# whoop65mm.net
KiCad netlist of a schematic drawn in EAGLE
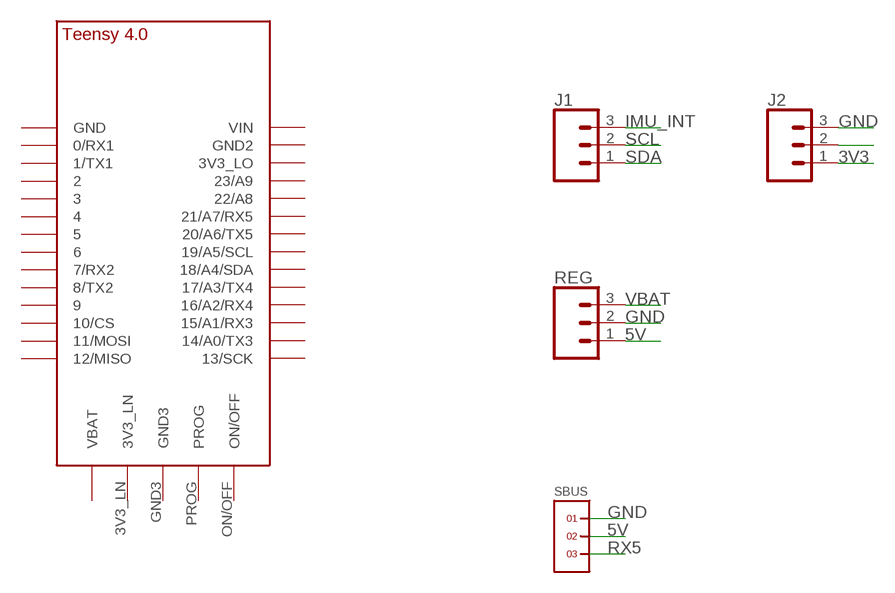
[diagram p0: schematic, sheet 1]

(export (version "E")
  (design (tool "Eeschema 10.0.6"))
  (components
    (comp (ref "J1")
      (value "CONN_031X03_NO_SILK")
      (footprint "eagle-import:1X03_NO_SILK")
      (libsource (lib "eagle-import") (part "CONN_031X03_NO_SILK"))
    )
    (comp (ref "J2")
      (value "CONN_031X03_NO_SILK")
      (footprint "eagle-import:1X03_NO_SILK")
      (libsource (lib "eagle-import") (part "CONN_031X03_NO_SILK"))
    )
    (comp (ref "REG")
      (value "CONN_031X03_NO_SILK")
      (footprint "eagle-import:1X03_NO_SILK")
      (libsource (lib "eagle-import") (part "CONN_031X03_NO_SILK"))
    )
    (comp (ref "SBUS")
      (value "1X3")
      (footprint "eagle-import:1X3")
      (libsource (lib "eagle-import") (part "1X3"))
    )
    (comp (ref "U$1")
      (value "TEENSY_4.0")
      (footprint "eagle-import:TEENSY_4.0")
      (libsource (lib "eagle-import") (part "TEENSY_4.0"))
    )
  )
  (nets
    (net (code "1") (name "/3V3") (class "Default")
      (node (ref "J2") (pin "1") (pinfunction "1_1") (pintype "passive"))
    )
    (net (code "2") (name "/5V") (class "Default")
      (node (ref "REG") (pin "1") (pinfunction "1_1") (pintype "passive"))
      (node (ref "SBUS") (pin "2") (pinfunction "2_2") (pintype "bidirectional"))
    )
    (net (code "3") (name "/GND") (class "Default")
      (node (ref "J2") (pin "3") (pinfunction "3_3") (pintype "passive"))
      (node (ref "REG") (pin "2") (pinfunction "2_2") (pintype "passive"))
      (node (ref "SBUS") (pin "1") (pinfunction "1_1") (pintype "bidirectional"))
    )
    (net (code "4") (name "/IMU_INT") (class "Default")
      (node (ref "J1") (pin "3") (pinfunction "3_3") (pintype "passive"))
    )
    (net (code "5") (name "/RX5") (class "Default")
      (node (ref "SBUS") (pin "3") (pinfunction "3_3") (pintype "bidirectional"))
    )
    (net (code "6") (name "/SCL") (class "Default")
      (node (ref "J1") (pin "2") (pinfunction "2_2") (pintype "passive"))
    )
    (net (code "7") (name "/SDA") (class "Default")
      (node (ref "J1") (pin "1") (pinfunction "1_1") (pintype "passive"))
    )
    (net (code "8") (name "/VBAT") (class "Default")
      (node (ref "REG") (pin "3") (pinfunction "3_3") (pintype "passive"))
    )
    (net (code "9") (name "unconnected-(J2-Pad2)") (class "Default")
      (node (ref "J2") (pin "2") (pinfunction "2_2") (pintype "passive"))
    )
    (net (code "10") (name "unconnected-(U$1-0{slash}RX1-Pad0{slash}RX)") (class "Default")
      (node (ref "U$1") (pin "0/RX") (pinfunction "0/RX1_0/RX") (pintype "bidirectional"))
    )
    (net (code "11") (name "unconnected-(U$1-1{slash}TX1-Pad1{slash}TX)") (class "Default")
      (node (ref "U$1") (pin "1/TX") (pinfunction "1/TX1_1/TX") (pintype "bidirectional"))
    )
    (net (code "12") (name "unconnected-(U$1-3-Pad3{slash}CANTX)") (class "Default")
      (node (ref "U$1") (pin "3/CANTX") (pinfunction "3_3/CANTX") (pintype "bidirectional"))
    )
    (net (code "13") (name "unconnected-(U$1-4-Pad4{slash}CANRX)") (class "Default")
      (node (ref "U$1") (pin "4/CANRX") (pinfunction "4_4/CANRX") (pintype "bidirectional"))
    )
    (net (code "14") (name "unconnected-(U$1-7{slash}RX2-Pad7)") (class "Default")
      (node (ref "U$1") (pin "7") (pinfunction "7/RX2_7") (pintype "bidirectional"))
    )
    (net (code "15") (name "unconnected-(U$1-8{slash}TX2-Pad8)") (class "Default")
      (node (ref "U$1") (pin "8") (pinfunction "8/TX2_8") (pintype "bidirectional"))
    )
    (net (code "16") (name "unconnected-(U$1-9-Pad9{slash}CS)") (class "Default")
      (node (ref "U$1") (pin "9/CS") (pinfunction "9_9/CS") (pintype "bidirectional"))
    )
    (net (code "17") (name "unconnected-(U$1-14{slash}A0{slash}TX3-Pad14{slash}A0)") (class "Default")
      (node (ref "U$1") (pin "14/A0") (pinfunction "14/A0/TX3_14/A0") (pintype "bidirectional"))
    )
    (net (code "18") (name "unconnected-(U$1-15{slash}A1{slash}RX3-Pad15{slash}A1)") (class "Default")
      (node (ref "U$1") (pin "15/A1") (pinfunction "15/A1/RX3_15/A1") (pintype "bidirectional"))
    )
    (net (code "19") (name "unconnected-(U$1-16{slash}A2{slash}RX4-Pad16{slash}A2)") (class "Default")
      (node (ref "U$1") (pin "16/A2") (pinfunction "16/A2/RX4_16/A2") (pintype "bidirectional"))
    )
    (net (code "20") (name "unconnected-(U$1-17{slash}A3{slash}TX4-Pad17{slash}A3)") (class "Default")
      (node (ref "U$1") (pin "17/A3") (pinfunction "17/A3/TX4_17/A3") (pintype "bidirectional"))
    )
    (net (code "21") (name "unconnected-(U$1-20{slash}A6{slash}TX5-Pad20{slash}A6)") (class "Default")
      (node (ref "U$1") (pin "20/A6") (pinfunction "20/A6/TX5_20/A6") (pintype "bidirectional"))
    )
    (net (code "22") (name "unconnected-(U$1-21{slash}A7{slash}RX5-Pad21{slash}A7)") (class "Default")
      (node (ref "U$1") (pin "21/A7") (pinfunction "21/A7/RX5_21/A7") (pintype "bidirectional"))
    )
    (net (code "23") (name "unconnected-(U$1-Pad2)") (class "Default")
      (node (ref "U$1") (pin "2") (pinfunction "2_2") (pintype "bidirectional"))
    )
    (net (code "24") (name "unconnected-(U$1-Pad3V3_LN)") (class "Default")
      (node (ref "U$1") (pin "3V3_LN") (pinfunction "3V3_LN_3V3_LN") (pintype "bidirectional"))
    )
    (net (code "25") (name "unconnected-(U$1-Pad3V3_LO)") (class "Default")
      (node (ref "U$1") (pin "3V3_LO") (pinfunction "3V3_LO_3V3_LO") (pintype "bidirectional"))
    )
    (net (code "26") (name "unconnected-(U$1-Pad5)") (class "Default")
      (node (ref "U$1") (pin "5") (pinfunction "5_5") (pintype "bidirectional"))
    )
    (net (code "27") (name "unconnected-(U$1-Pad6)") (class "Default")
      (node (ref "U$1") (pin "6") (pinfunction "6_6") (pintype "bidirectional"))
    )
    (net (code "28") (name "unconnected-(U$1-Pad10{slash}CS)") (class "Default")
      (node (ref "U$1") (pin "10/CS") (pinfunction "10/CS_10/CS") (pintype "bidirectional"))
    )
    (net (code "29") (name "unconnected-(U$1-Pad11{slash}MOSI)") (class "Default")
      (node (ref "U$1") (pin "11/MOSI") (pinfunction "11/MOSI_11/MOSI") (pintype "bidirectional"))
    )
    (net (code "30") (name "unconnected-(U$1-Pad12{slash}MISO)") (class "Default")
      (node (ref "U$1") (pin "12/MISO") (pinfunction "12/MISO_12/MISO") (pintype "bidirectional"))
    )
    (net (code "31") (name "unconnected-(U$1-Pad13{slash}SCK)") (class "Default")
      (node (ref "U$1") (pin "13/SCK") (pinfunction "13/SCK_13/SCK") (pintype "bidirectional"))
    )
    (net (code "32") (name "unconnected-(U$1-Pad18{slash}A4{slash}SDA)") (class "Default")
      (node (ref "U$1") (pin "18/A4/SDA") (pinfunction "18/A4/SDA_18/A4/SDA") (pintype "bidirectional"))
    )
    (net (code "33") (name "unconnected-(U$1-Pad19{slash}A5{slash}SCL)") (class "Default")
      (node (ref "U$1") (pin "19/A5/SCL") (pinfunction "19/A5/SCL_19/A5/SCL") (pintype "bidirectional"))
    )
    (net (code "34") (name "unconnected-(U$1-Pad22{slash}A8)") (class "Default")
      (node (ref "U$1") (pin "22/A8") (pinfunction "22/A8_22/A8") (pintype "bidirectional"))
    )
    (net (code "35") (name "unconnected-(U$1-Pad23{slash}A9)") (class "Default")
      (node (ref "U$1") (pin "23/A9") (pinfunction "23/A9_23/A9") (pintype "bidirectional"))
    )
    (net (code "36") (name "unconnected-(U$1-PadGND)") (class "Default")
      (node (ref "U$1") (pin "GND") (pinfunction "GND_GND") (pintype "bidirectional"))
    )
    (net (code "37") (name "unconnected-(U$1-PadGND2)") (class "Default")
      (node (ref "U$1") (pin "GND2") (pinfunction "GND2_GND2") (pintype "bidirectional"))
    )
    (net (code "38") (name "unconnected-(U$1-PadGND3)") (class "Default")
      (node (ref "U$1") (pin "GND3") (pinfunction "GND3_GND3") (pintype "bidirectional"))
    )
    (net (code "39") (name "unconnected-(U$1-PadON{slash}OFF)") (class "Default")
      (node (ref "U$1") (pin "ON/OFF") (pinfunction "ON/OFF_ON/OFF") (pintype "bidirectional"))
    )
    (net (code "40") (name "unconnected-(U$1-PadPROG)") (class "Default")
      (node (ref "U$1") (pin "PROG") (pinfunction "PROG_PROG") (pintype "bidirectional"))
    )
    (net (code "41") (name "unconnected-(U$1-PadVIN)") (class "Default")
      (node (ref "U$1") (pin "VIN") (pinfunction "VIN_VIN") (pintype "bidirectional"))
    )
    (net (code "42") (name "unconnected-(U$1-VBAT-PadVBAT\\)") (class "Default")
      (node (ref "U$1") (pin "VBAT\\") (pinfunction "VBAT_VBAT\\") (pintype "bidirectional"))
    )
  )
)
